# Subsytemintrosychematic.net
KiCad netlist of a schematic drawn in Altium Designer
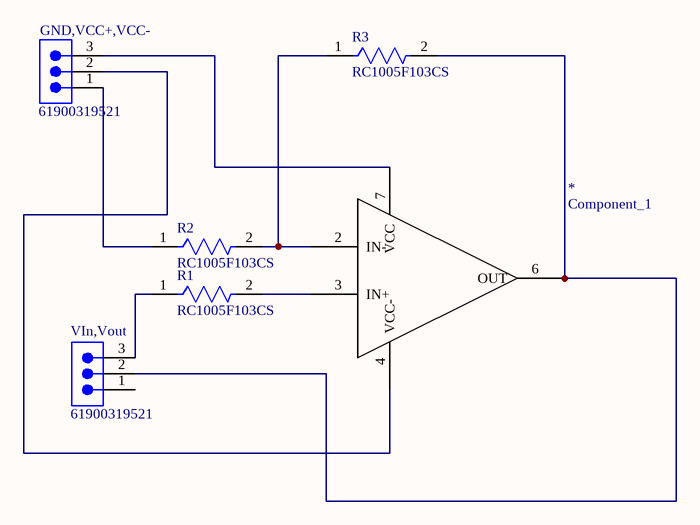
[diagram p0: Subsytemintrosychematic.SchDoc]

(export (version "E")
  (design (tool "Eeschema 10.0.6"))
  (components
    (comp (ref "*")
      (value "Component_1")
      (footprint "PCBComponent_1")
      (libsource (lib "SymbolSubSystemIntroProj") (part "Component_1"))
    )
    (comp (ref "GND,VCC+,VCC-")
      (value "61900319521")
      (footprint "61900319521")
      (libsource (lib "Copy of connewctoreal") (part "CMP-1502-00600-2"))
    )
    (comp (ref "R1")
      (value "RC1005F103CS")
      (footprint "FP-RC1005-IPC_A")
      (description "Res Thick Film 0402 10kΩ 1% 0.063W ±100ppm/°C Molded SMD T/R")
      (fields (field (name "TOLERANCE") "1%"))
      (libsource (lib "ResisitorSymbol") (part "CMP-13261-004522-1"))
    )
    (comp (ref "R2")
      (value "RC1005F103CS")
      (footprint "FP-RC1005-IPC_A")
      (description "Res Thick Film 0402 10kΩ 1% 0.063W ±100ppm/°C Molded SMD T/R")
      (fields (field (name "TOLERANCE") "1%"))
      (libsource (lib "ResisitorSymbol") (part "CMP-13261-004522-1"))
    )
    (comp (ref "R3")
      (value "RC1005F103CS")
      (footprint "FP-RC1005-IPC_A")
      (description "Res Thick Film 0402 10kΩ 1% 0.063W ±100ppm/°C Molded SMD T/R")
      (fields (field (name "TOLERANCE") "1%"))
      (libsource (lib "ResisitorSymbol") (part "CMP-13261-004522-1"))
    )
    (comp (ref "VIn,Vout")
      (value "61900319521")
      (footprint "61900319521")
      (libsource (lib "Copy of connewctoreal") (part "CMP-1502-00600-2"))
    )
  )
  (nets
    (net (code "1") (name "Net-(*-IN+)") (class "Default")
      (node (ref "*") (pin "3") (pinfunction "IN+_3") (pintype "passive"))
      (node (ref "R1") (pin "2") (pinfunction "2_2") (pintype "passive"))
    )
    (net (code "2") (name "Net-(*-IN-)") (class "Default")
      (node (ref "*") (pin "2") (pinfunction "IN-_2") (pintype "passive"))
      (node (ref "R2") (pin "2") (pinfunction "2_2") (pintype "passive"))
      (node (ref "R3") (pin "1") (pinfunction "1_1") (pintype "passive"))
    )
    (net (code "3") (name "Net-(*-OUT)") (class "Default")
      (node (ref "*") (pin "6") (pinfunction "OUT_6") (pintype "passive"))
      (node (ref "R3") (pin "2") (pinfunction "2_2") (pintype "passive"))
      (node (ref "VIn,Vout") (pin "2") (pinfunction "2_2") (pintype "passive"))
    )
    (net (code "4") (name "Net-(*-VCC)") (class "Default")
      (node (ref "*") (pin "7") (pinfunction "VCC_7") (pintype "passive"))
      (node (ref "GND,VCC+,VCC-") (pin "3") (pinfunction "3_3") (pintype "passive"))
    )
    (net (code "5") (name "Net-(*-VCC-)") (class "Default")
      (node (ref "*") (pin "4") (pinfunction "VCC-_4") (pintype "passive"))
      (node (ref "GND,VCC+,VCC-") (pin "2") (pinfunction "2_2") (pintype "passive"))
    )
    (net (code "6") (name "Net-(GND,VCC+,VCC--Pad1)") (class "Default")
      (node (ref "GND,VCC+,VCC-") (pin "1") (pinfunction "1_1") (pintype "passive"))
      (node (ref "R2") (pin "1") (pinfunction "1_1") (pintype "passive"))
    )
    (net (code "7") (name "Net-(R1-Pad1)") (class "Default")
      (node (ref "R1") (pin "1") (pinfunction "1_1") (pintype "passive"))
      (node (ref "VIn,Vout") (pin "3") (pinfunction "3_3") (pintype "passive"))
    )
    (net (code "8") (name "unconnected-(VIn,Vout-Pad1)") (class "Default")
      (node (ref "VIn,Vout") (pin "1") (pinfunction "1_1") (pintype "passive"))
    )
  )
)
